# Mazebot.net
KiCad netlist of a schematic drawn in Altium Designer
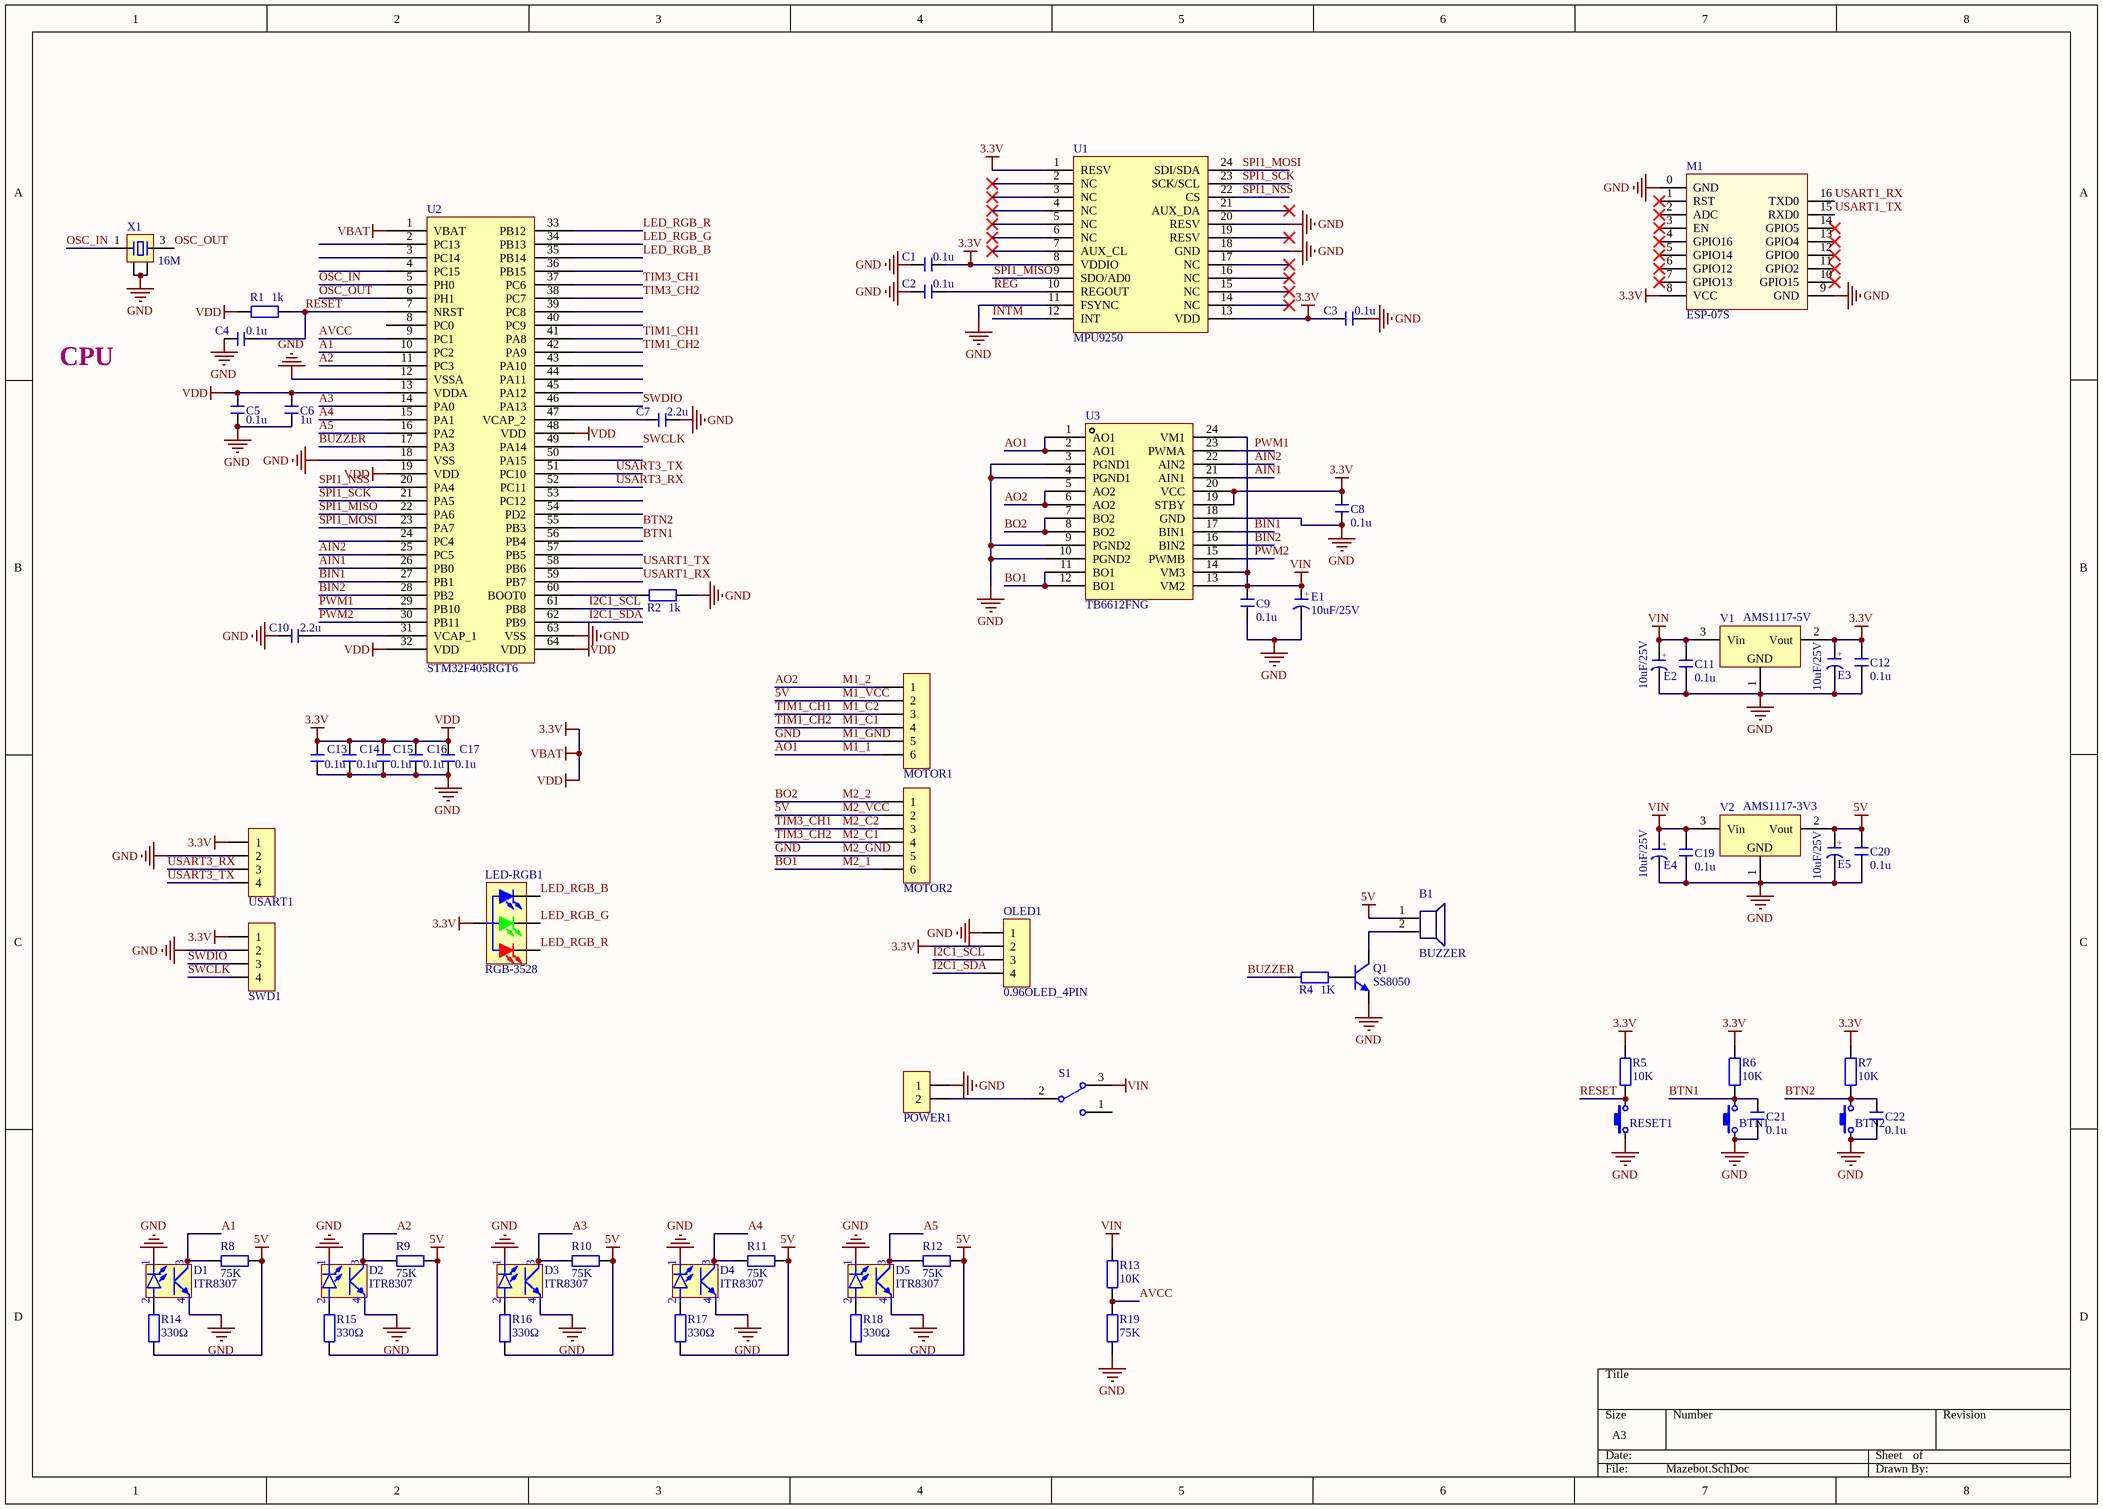
[diagram p0: Mazebot.SchDoc]

(export (version "E")
  (design (tool "Eeschema 10.0.6"))
  (components
    (comp (ref "B1")
      (value "BUZZER")
      (footprint "BUZ-TH_BD9.0-P4.00-D1.0-FD")
      (description "小蜂鸣器 脚距4mm")
      (libsource (lib "0.0 - YltsSchlib") (part "BUZZER"))
    )
    (comp (ref "BTN1")
      (value "ButtonTACT_3x4x2_180")
      (footprint "ButtonTACT_3x4x2_180H")
      (description "Button")
      (libsource (lib "0.0 - YltsSchlib") (part "ButtonTACT_3x4x2_180"))
    )
    (comp (ref "BTN2")
      (value "ButtonTACT_3x4x2_180")
      (footprint "ButtonTACT_3x4x2_180H")
      (description "Button")
      (libsource (lib "0.0 - YltsSchlib") (part "ButtonTACT_3x4x2_180"))
    )
    (comp (ref "C1")
      (value "0.1u")
      (footprint "0603-CAP")
      (description "贴片电容")
      (libsource (lib "0.1 - 电阻-电容-电感") (part "C"))
    )
    (comp (ref "C2")
      (value "0.1u")
      (footprint "0603-CAP")
      (description "贴片电容")
      (libsource (lib "0.1 - 电阻-电容-电感") (part "C"))
    )
    (comp (ref "C3")
      (value "0.1u")
      (footprint "0603-CAP")
      (description "贴片电容")
      (libsource (lib "0.1 - 电阻-电容-电感") (part "C"))
    )
    (comp (ref "C4")
      (value "0.1u")
      (footprint "0603-CAP")
      (description "贴片电容")
      (libsource (lib "0.1 - 电阻-电容-电感") (part "C"))
    )
    (comp (ref "C5")
      (value "0.1u")
      (footprint "0603-CAP")
      (description "贴片电容")
      (libsource (lib "0.1 - 电阻-电容-电感") (part "C"))
    )
    (comp (ref "C6")
      (value "1u")
      (footprint "0603-CAP")
      (description "贴片电容")
      (libsource (lib "0.1 - 电阻-电容-电感") (part "C"))
    )
    (comp (ref "C7")
      (value "2.2u")
      (footprint "0603-CAP")
      (description "贴片电容")
      (libsource (lib "0.1 - 电阻-电容-电感") (part "C"))
    )
    (comp (ref "C8")
      (value "0.1u")
      (footprint "0603-CAP")
      (description "贴片电容")
      (libsource (lib "0.1 - 电阻-电容-电感") (part "C"))
    )
    (comp (ref "C9")
      (value "0.1u")
      (footprint "0603-CAP")
      (description "贴片电容")
      (libsource (lib "0.1 - 电阻-电容-电感") (part "C"))
    )
    (comp (ref "C10")
      (value "2.2u")
      (footprint "0603-CAP")
      (description "贴片电容")
      (libsource (lib "0.1 - 电阻-电容-电感") (part "C"))
    )
    (comp (ref "C11")
      (value "0.1u")
      (footprint "0603-CAP")
      (description "贴片电容")
      (libsource (lib "0.1 - 电阻-电容-电感") (part "C"))
    )
    (comp (ref "C12")
      (value "0.1u")
      (footprint "0603-CAP")
      (description "贴片电容")
      (libsource (lib "0.1 - 电阻-电容-电感") (part "C"))
    )
    (comp (ref "C13")
      (value "0.1u")
      (footprint "0603-CAP")
      (description "贴片电容")
      (libsource (lib "0.1 - 电阻-电容-电感") (part "C"))
    )
    (comp (ref "C14")
      (value "0.1u")
      (footprint "0603-CAP")
      (description "贴片电容")
      (libsource (lib "0.1 - 电阻-电容-电感") (part "C"))
    )
    (comp (ref "C15")
      (value "0.1u")
      (footprint "0603-CAP")
      (description "贴片电容")
      (libsource (lib "0.1 - 电阻-电容-电感") (part "C"))
    )
    (comp (ref "C16")
      (value "0.1u")
      (footprint "0603-CAP")
      (description "贴片电容")
      (libsource (lib "0.1 - 电阻-电容-电感") (part "C"))
    )
    (comp (ref "C17")
      (value "0.1u")
      (footprint "0603-CAP")
      (description "贴片电容")
      (libsource (lib "0.1 - 电阻-电容-电感") (part "C"))
    )
    (comp (ref "C19")
      (value "0.1u")
      (footprint "0603-CAP")
      (description "贴片电容")
      (libsource (lib "0.1 - 电阻-电容-电感") (part "C"))
    )
    (comp (ref "C20")
      (value "0.1u")
      (footprint "0603-CAP")
      (description "贴片电容")
      (libsource (lib "0.1 - 电阻-电容-电感") (part "C"))
    )
    (comp (ref "C21")
      (value "0.1u")
      (footprint "0603-CAP")
      (description "贴片电容")
      (libsource (lib "0.1 - 电阻-电容-电感") (part "C"))
    )
    (comp (ref "C22")
      (value "0.1u")
      (footprint "0603-CAP")
      (description "贴片电容")
      (libsource (lib "0.1 - 电阻-电容-电感") (part "C"))
    )
    (comp (ref "D1")
      (value "ITR8307")
      (footprint "OPTO-SMD_ITR8307")
      (description "反射式光电开关 收发一体")
      (libsource (lib "0.0 - YltsSchlib") (part "ITR8307"))
    )
    (comp (ref "D2")
      (value "ITR8307")
      (footprint "OPTO-SMD_ITR8307")
      (description "反射式光电开关 收发一体")
      (libsource (lib "0.0 - YltsSchlib") (part "ITR8307"))
    )
    (comp (ref "D3")
      (value "ITR8307")
      (footprint "OPTO-SMD_ITR8307")
      (description "反射式光电开关 收发一体")
      (libsource (lib "0.0 - YltsSchlib") (part "ITR8307"))
    )
    (comp (ref "D4")
      (value "ITR8307")
      (footprint "OPTO-SMD_ITR8307")
      (description "反射式光电开关 收发一体")
      (libsource (lib "0.0 - YltsSchlib") (part "ITR8307"))
    )
    (comp (ref "D5")
      (value "ITR8307")
      (footprint "OPTO-SMD_ITR8307")
      (description "反射式光电开关 收发一体")
      (libsource (lib "0.0 - YltsSchlib") (part "ITR8307"))
    )
    (comp (ref "E1")
      (value "10uF/25V")
      (footprint "3528-CAP")
      (description "贴片钽电容")
      (libsource (lib "0.1 - 电阻-电容-电感") (part "CT"))
    )
    (comp (ref "E2")
      (value "10uF/25V")
      (footprint "3528-CAP")
      (description "贴片钽电容")
      (libsource (lib "0.1 - 电阻-电容-电感") (part "CT"))
    )
    (comp (ref "E3")
      (value "10uF/25V")
      (footprint "3528-CAP")
      (description "贴片钽电容")
      (libsource (lib "0.1 - 电阻-电容-电感") (part "CT"))
    )
    (comp (ref "E4")
      (value "10uF/25V")
      (footprint "3528-CAP")
      (description "贴片钽电容")
      (libsource (lib "0.1 - 电阻-电容-电感") (part "CT"))
    )
    (comp (ref "E5")
      (value "10uF/25V")
      (footprint "3528-CAP")
      (description "贴片钽电容")
      (libsource (lib "0.1 - 电阻-电容-电感") (part "CT"))
    )
    (comp (ref "LED-RGB1")
      (value "RGB-3528")
      (footprint "LED 3528-4Pin")
      (description "3528三基色LED")
      (fields (field (name "版权归属") "封装库来自淘宝 ID：黄晶宝石"))
      (libsource (lib "0.3 - LED发光二极管") (part "LED-RGB 3528"))
    )
    (comp (ref "M1")
      (value "ESP-07S")
      (footprint "ESP-07S")
      (libsource (lib "0.0 - YltsSchlib") (part "ESP-07S"))
    )
    (comp (ref "MOTOR1")
      (value "HDR-1X6")
      (footprint "HDR2.54-M-LI-6P")
      (description "6P接插件")
      (fields (field (name "版权归属") "封装库来自淘宝 ID：黄晶宝石"))
      (libsource (lib "5.3 - 接插件-脚距2.54 (100mil) ") (part "Header 6"))
    )
    (comp (ref "MOTOR2")
      (value "HDR-1X6")
      (footprint "HDR2.54-M-LI-6P")
      (description "6P接插件")
      (fields (field (name "版权归属") "封装库来自淘宝 ID：黄晶宝石"))
      (libsource (lib "5.3 - 接插件-脚距2.54 (100mil) ") (part "Header 6"))
    )
    (comp (ref "OLED1")
      (value "0.96OLED_4PIN")
      (footprint "0.96OLED_4PIN")
      (libsource (lib "0.0 - YltsSchlib") (part "0.96OLED_4PIN"))
    )
    (comp (ref "POWER1")
      (value "HDR-1X2")
      (footprint "XH2.54-LI-2P")
      (description "2P接插件")
      (fields (field (name "版权归属") "封装库来自淘宝 ID：黄晶宝石"))
      (libsource (lib "5.3 - 接插件-脚距2.54 (100mil) ") (part "Header 2"))
    )
    (comp (ref "Q1")
      (value "SS8050")
      (footprint "SOT23-3N")
      (description "高频放大-NPN型")
      (fields (field (name "版权归属") "封装库来自淘宝 ID：黄晶宝石"))
      (libsource (lib "0.4 - 三极管") (part "8050-SMD"))
    )
    (comp (ref "R1")
      (value "1k")
      (footprint "0603-RES")
      (description "贴片电阻")
      (fields (field (name "版权归属") "来自淘宝 ID：黄晶宝石"))
      (libsource (lib "0.1 - 电阻-电容-电感") (part "R"))
    )
    (comp (ref "R2")
      (value "1k")
      (footprint "0603-RES")
      (description "贴片电阻")
      (fields (field (name "版权归属") "来自淘宝 ID：黄晶宝石"))
      (libsource (lib "0.1 - 电阻-电容-电感") (part "R"))
    )
    (comp (ref "R4")
      (value "1K")
      (footprint "0603-RES")
      (description "贴片电阻")
      (fields (field (name "版权归属") "来自淘宝 ID：黄晶宝石"))
      (libsource (lib "0.1 - 电阻-电容-电感") (part "R"))
    )
    (comp (ref "R5")
      (value "10K")
      (footprint "0603-RES")
      (description "贴片电阻")
      (fields (field (name "版权归属") "来自淘宝 ID：黄晶宝石"))
      (libsource (lib "0.1 - 电阻-电容-电感") (part "R"))
    )
    (comp (ref "R6")
      (value "10K")
      (footprint "0603-RES")
      (description "贴片电阻")
      (fields (field (name "版权归属") "来自淘宝 ID：黄晶宝石"))
      (libsource (lib "0.1 - 电阻-电容-电感") (part "R"))
    )
    (comp (ref "R7")
      (value "10K")
      (footprint "0603-RES")
      (description "贴片电阻")
      (fields (field (name "版权归属") "来自淘宝 ID：黄晶宝石"))
      (libsource (lib "0.1 - 电阻-电容-电感") (part "R"))
    )
    (comp (ref "R8")
      (value "75K")
      (footprint "0603-RES")
      (description "贴片电阻")
      (fields (field (name "版权归属") "来自淘宝 ID：黄晶宝石"))
      (libsource (lib "0.1 - 电阻-电容-电感") (part "R"))
    )
    (comp (ref "R9")
      (value "75K")
      (footprint "0603-RES")
      (description "贴片电阻")
      (fields (field (name "版权归属") "来自淘宝 ID：黄晶宝石"))
      (libsource (lib "0.1 - 电阻-电容-电感") (part "R"))
    )
    (comp (ref "R10")
      (value "75K")
      (footprint "0603-RES")
      (description "贴片电阻")
      (fields (field (name "版权归属") "来自淘宝 ID：黄晶宝石"))
      (libsource (lib "0.1 - 电阻-电容-电感") (part "R"))
    )
    (comp (ref "R11")
      (value "75K")
      (footprint "0603-RES")
      (description "贴片电阻")
      (fields (field (name "版权归属") "来自淘宝 ID：黄晶宝石"))
      (libsource (lib "0.1 - 电阻-电容-电感") (part "R"))
    )
    (comp (ref "R12")
      (value "75K")
      (footprint "0603-RES")
      (description "贴片电阻")
      (fields (field (name "版权归属") "来自淘宝 ID：黄晶宝石"))
      (libsource (lib "0.1 - 电阻-电容-电感") (part "R"))
    )
    (comp (ref "R13")
      (value "10K")
      (footprint "0603-RES")
      (description "贴片电阻")
      (fields (field (name "版权归属") "来自淘宝 ID：黄晶宝石"))
      (libsource (lib "0.1 - 电阻-电容-电感") (part "R"))
    )
    (comp (ref "R14")
      (value "330Ω")
      (footprint "0603-RES")
      (description "贴片电阻")
      (fields (field (name "版权归属") "来自淘宝 ID：黄晶宝石"))
      (libsource (lib "0.1 - 电阻-电容-电感") (part "R"))
    )
    (comp (ref "R15")
      (value "330Ω")
      (footprint "0603-RES")
      (description "贴片电阻")
      (fields (field (name "版权归属") "来自淘宝 ID：黄晶宝石"))
      (libsource (lib "0.1 - 电阻-电容-电感") (part "R"))
    )
    (comp (ref "R16")
      (value "330Ω")
      (footprint "0603-RES")
      (description "贴片电阻")
      (fields (field (name "版权归属") "来自淘宝 ID：黄晶宝石"))
      (libsource (lib "0.1 - 电阻-电容-电感") (part "R"))
    )
    (comp (ref "R17")
      (value "330Ω")
      (footprint "0603-RES")
      (description "贴片电阻")
      (fields (field (name "版权归属") "来自淘宝 ID：黄晶宝石"))
      (libsource (lib "0.1 - 电阻-电容-电感") (part "R"))
    )
    (comp (ref "R18")
      (value "330Ω")
      (footprint "0603-RES")
      (description "贴片电阻")
      (fields (field (name "版权归属") "来自淘宝 ID：黄晶宝石"))
      (libsource (lib "0.1 - 电阻-电容-电感") (part "R"))
    )
    (comp (ref "R19")
      (value "75K")
      (footprint "0603-RES")
      (description "贴片电阻")
      (fields (field (name "版权归属") "来自淘宝 ID：黄晶宝石"))
      (libsource (lib "0.1 - 电阻-电容-电感") (part "R"))
    )
    (comp (ref "RESET1")
      (value "ButtonTACT_3x4x2_180")
      (footprint "ButtonTACT_3x4x2_180H")
      (description "Button")
      (libsource (lib "0.0 - YltsSchlib") (part "ButtonTACT_3x4x2_180"))
    )
    (comp (ref "S1")
      (value "SwitchSPDT_4.3x8.6_D90")
      (footprint "SwitchSPDT_4.3X8.6_D90")
      (description "Switch")
      (libsource (lib "0.0 - YltsSchlib") (part "SwitchSPDT_4.3x8.6_D90"))
    )
    (comp (ref "SWD1")
      (value "HDR-1X4")
      (footprint "HDR2.54-LI-4P")
      (description "4P接插件")
      (fields (field (name "版权归属") "封装库来自淘宝 ID：黄晶宝石"))
      (libsource (lib "5.3 - 接插件-脚距2.54 (100mil) ") (part "Header 4"))
    )
    (comp (ref "U1")
      (value "MPU9250")
      (footprint "QFN_P0.4_24")
      (description "9轴姿态传感器")
      (libsource (lib "0.0 - YltsSchlib") (part "MPU925x"))
    )
    (comp (ref "U2")
      (value "STM32F405RGT6")
      (footprint "LQFP-64")
      (libsource (lib "陀螺仪 元件") (part "STM32F405RGT7"))
    )
    (comp (ref "U3")
      (value "TB6612FNG")
      (footprint "SSOP24_N")
      (description "双直流电机驱动器")
      (libsource (lib "0.0 - YltsSchlib") (part "TB6612FNG"))
    )
    (comp (ref "USART1")
      (value "HDR-1X4")
      (footprint "HDR2.54-LI-4P")
      (description "4P接插件")
      (fields (field (name "版权归属") "封装库来自淘宝 ID：黄晶宝石"))
      (libsource (lib "5.3 - 接插件-脚距2.54 (100mil) ") (part "Header 4"))
    )
    (comp (ref "V1")
      (value "AMS1117-5V")
      (footprint "SOT223_L")
      (description "三端稳压芯片")
      (libsource (lib "1.1 - 电源类芯片") (part "AMS1117"))
    )
    (comp (ref "V2")
      (value "AMS1117-3V3")
      (footprint "SOT223_L")
      (description "三端稳压芯片")
      (libsource (lib "1.1 - 电源类芯片") (part "AMS1117"))
    )
    (comp (ref "X1")
      (value "16M")
      (footprint "OSC 3225-4P")
      (description "4脚无源晶振")
      (fields (field (name "版权归属") "封装库来自淘宝卖家 ID：黄晶宝石"))
      (libsource (lib "2.0 - 保险丝-晶振-光耦") (part "XTAL-4P"))
    )
  )
  (nets
    (net (code "1") (name "/A1") (class "Default")
      (node (ref "D1") (pin "3") (pinfunction "K_3") (pintype "passive"))
      (node (ref "R8") (pin "2") (pinfunction "2_2") (pintype "passive"))
      (node (ref "U2") (pin "10") (pinfunction "PC2_10") (pintype "passive"))
    )
    (net (code "2") (name "/A2") (class "Default")
      (node (ref "D2") (pin "3") (pinfunction "K_3") (pintype "passive"))
      (node (ref "R9") (pin "2") (pinfunction "2_2") (pintype "passive"))
      (node (ref "U2") (pin "11") (pinfunction "PC3_11") (pintype "passive"))
    )
    (net (code "3") (name "/A3") (class "Default")
      (node (ref "D3") (pin "3") (pinfunction "K_3") (pintype "passive"))
      (node (ref "R10") (pin "2") (pinfunction "2_2") (pintype "passive"))
      (node (ref "U2") (pin "14") (pinfunction "PA0_14") (pintype "passive"))
    )
    (net (code "4") (name "/A4") (class "Default")
      (node (ref "D4") (pin "3") (pinfunction "K_3") (pintype "passive"))
      (node (ref "R11") (pin "2") (pinfunction "2_2") (pintype "passive"))
      (node (ref "U2") (pin "15") (pinfunction "PA1_15") (pintype "passive"))
    )
    (net (code "5") (name "/A5") (class "Default")
      (node (ref "D5") (pin "3") (pinfunction "K_3") (pintype "passive"))
      (node (ref "R12") (pin "2") (pinfunction "2_2") (pintype "passive"))
      (node (ref "U2") (pin "16") (pinfunction "PA2_16") (pintype "passive"))
    )
    (net (code "6") (name "/AIN1") (class "Default")
      (node (ref "U2") (pin "26") (pinfunction "PB0_26") (pintype "passive"))
      (node (ref "U3") (pin "21") (pinfunction "AIN1_21") (pintype "passive"))
    )
    (net (code "7") (name "/AIN2") (class "Default")
      (node (ref "U2") (pin "25") (pinfunction "PC5_25") (pintype "passive"))
      (node (ref "U3") (pin "22") (pinfunction "AIN2_22") (pintype "passive"))
    )
    (net (code "8") (name "/AO1") (class "Default")
      (node (ref "MOTOR1") (pin "6") (pinfunction "6_6") (pintype "passive"))
      (node (ref "U3") (pin "1") (pinfunction "AO1_1") (pintype "passive"))
      (node (ref "U3") (pin "2") (pinfunction "AO1_2") (pintype "passive"))
    )
    (net (code "9") (name "/AO2") (class "Default")
      (node (ref "MOTOR1") (pin "1") (pinfunction "1_1") (pintype "passive"))
      (node (ref "U3") (pin "5") (pinfunction "AO2_5") (pintype "passive"))
      (node (ref "U3") (pin "6") (pinfunction "AO2_6") (pintype "passive"))
    )
    (net (code "10") (name "/AVCC") (class "Default")
      (node (ref "R13") (pin "2") (pinfunction "2_2") (pintype "passive"))
      (node (ref "R19") (pin "1") (pinfunction "1_1") (pintype "passive"))
      (node (ref "U2") (pin "9") (pinfunction "PC1_9") (pintype "passive"))
    )
    (net (code "11") (name "/BIN1") (class "Default")
      (node (ref "U2") (pin "27") (pinfunction "PB1_27") (pintype "passive"))
      (node (ref "U3") (pin "17") (pinfunction "BIN1_17") (pintype "passive"))
    )
    (net (code "12") (name "/BIN2") (class "Default")
      (node (ref "U2") (pin "28") (pinfunction "PB2_28") (pintype "passive"))
      (node (ref "U3") (pin "16") (pinfunction "BIN2_16") (pintype "passive"))
    )
    (net (code "13") (name "/BO1") (class "Default")
      (node (ref "MOTOR2") (pin "6") (pinfunction "6_6") (pintype "passive"))
      (node (ref "U3") (pin "11") (pinfunction "BO1_11") (pintype "passive"))
      (node (ref "U3") (pin "12") (pinfunction "BO1_12") (pintype "passive"))
    )
    (net (code "14") (name "/BO2") (class "Default")
      (node (ref "MOTOR2") (pin "1") (pinfunction "1_1") (pintype "passive"))
      (node (ref "U3") (pin "7") (pinfunction "BO2_7") (pintype "passive"))
      (node (ref "U3") (pin "8") (pinfunction "BO2_8") (pintype "passive"))
    )
    (net (code "15") (name "/BTN1") (class "Default")
      (node (ref "BTN1") (pin "2") (pinfunction "2_2") (pintype "passive"))
      (node (ref "C21") (pin "2") (pinfunction "2_2") (pintype "passive"))
      (node (ref "R6") (pin "2") (pinfunction "2_2") (pintype "passive"))
      (node (ref "U2") (pin "56") (pinfunction "PB4_56") (pintype "passive"))
    )
    (net (code "16") (name "/BTN2") (class "Default")
      (node (ref "BTN2") (pin "2") (pinfunction "2_2") (pintype "passive"))
      (node (ref "C22") (pin "2") (pinfunction "2_2") (pintype "passive"))
      (node (ref "R7") (pin "2") (pinfunction "2_2") (pintype "passive"))
      (node (ref "U2") (pin "55") (pinfunction "PB3_55") (pintype "passive"))
    )
    (net (code "17") (name "/BUZZER") (class "Default")
      (node (ref "R4") (pin "2") (pinfunction "2_2") (pintype "passive"))
      (node (ref "U2") (pin "17") (pinfunction "PA3_17") (pintype "passive"))
    )
    (net (code "18") (name "/I2C1_SCL") (class "Default")
      (node (ref "OLED1") (pin "3") (pinfunction "3_3") (pintype "passive"))
      (node (ref "U2") (pin "61") (pinfunction "PB8_61") (pintype "passive"))
    )
    (net (code "19") (name "/I2C1_SDA") (class "Default")
      (node (ref "OLED1") (pin "4") (pinfunction "4_4") (pintype "passive"))
      (node (ref "U2") (pin "62") (pinfunction "PB9_62") (pintype "passive"))
    )
    (net (code "20") (name "/INTM") (class "Default")
      (node (ref "U1") (pin "12") (pinfunction "INT_12") (pintype "passive"))
    )
    (net (code "21") (name "/LED_RGB_B") (class "Default")
      (node (ref "LED-RGB1") (pin "3") (pinfunction "BULE_K_3") (pintype "passive"))
      (node (ref "U2") (pin "35") (pinfunction "PB14_35") (pintype "passive"))
    )
    (net (code "22") (name "/LED_RGB_G") (class "Default")
      (node (ref "LED-RGB1") (pin "2") (pinfunction "GREEN_K_2") (pintype "passive"))
      (node (ref "U2") (pin "34") (pinfunction "PB13_34") (pintype "passive"))
    )
    (net (code "23") (name "/LED_RGB_R") (class "Default")
      (node (ref "LED-RGB1") (pin "1") (pinfunction "RED_K_1") (pintype "passive"))
      (node (ref "U2") (pin "33") (pinfunction "PB12_33") (pintype "passive"))
    )
    (net (code "24") (name "/M1_C1") (class "Default")
      (node (ref "MOTOR1") (pin "4") (pinfunction "4_4") (pintype "passive"))
      (node (ref "U2") (pin "42") (pinfunction "PA9_42") (pintype "passive"))
    )
    (net (code "25") (name "/M1_C2") (class "Default")
      (node (ref "MOTOR1") (pin "3") (pinfunction "3_3") (pintype "passive"))
      (node (ref "U2") (pin "41") (pinfunction "PA8_41") (pintype "passive"))
    )
    (net (code "26") (name "/M2_C1") (class "Default")
      (node (ref "MOTOR2") (pin "4") (pinfunction "4_4") (pintype "passive"))
      (node (ref "U2") (pin "38") (pinfunction "PC7_38") (pintype "passive"))
    )
    (net (code "27") (name "/M2_C2") (class "Default")
      (node (ref "MOTOR2") (pin "3") (pinfunction "3_3") (pintype "passive"))
      (node (ref "U2") (pin "37") (pinfunction "PC6_37") (pintype "passive"))
    )
    (net (code "28") (name "/OSC_IN") (class "Default")
      (node (ref "U2") (pin "5") (pinfunction "PH0_5") (pintype "passive"))
      (node (ref "X1") (pin "1") (pinfunction "1_1") (pintype "passive"))
    )
    (net (code "29") (name "/OSC_OUT") (class "Default")
      (node (ref "U2") (pin "6") (pinfunction "PH1_6") (pintype "passive"))
      (node (ref "X1") (pin "3") (pinfunction "3_3") (pintype "passive"))
    )
    (net (code "30") (name "/PWM1") (class "Default")
      (node (ref "U2") (pin "29") (pinfunction "PB10_29") (pintype "passive"))
      (node (ref "U3") (pin "23") (pinfunction "PWMA_23") (pintype "passive"))
    )
    (net (code "31") (name "/PWM2") (class "Default")
      (node (ref "U2") (pin "30") (pinfunction "PB11_30") (pintype "passive"))
      (node (ref "U3") (pin "15") (pinfunction "PWMB_15") (pintype "passive"))
    )
    (net (code "32") (name "/REG") (class "Default")
      (node (ref "C2") (pin "1") (pinfunction "1_1") (pintype "passive"))
      (node (ref "U1") (pin "10") (pinfunction "REGOUT_10") (pintype "passive"))
    )
    (net (code "33") (name "/RESET") (class "Default")
      (node (ref "C4") (pin "1") (pinfunction "1_1") (pintype "passive"))
      (node (ref "R1") (pin "1") (pinfunction "1_1") (pintype "passive"))
      (node (ref "R5") (pin "2") (pinfunction "2_2") (pintype "passive"))
      (node (ref "RESET1") (pin "2") (pinfunction "2_2") (pintype "passive"))
      (node (ref "U2") (pin "7") (pinfunction "NRST_7") (pintype "passive"))
    )
    (net (code "34") (name "/SPI1_MISO") (class "Default")
      (node (ref "U1") (pin "9") (pinfunction "SDO/AD0_9") (pintype "passive"))
      (node (ref "U2") (pin "22") (pinfunction "PA6_22") (pintype "passive"))
    )
    (net (code "35") (name "/SPI1_MOSI") (class "Default")
      (node (ref "U1") (pin "24") (pinfunction "SDI/SDA_24") (pintype "passive"))
      (node (ref "U2") (pin "23") (pinfunction "PA7_23") (pintype "passive"))
    )
    (net (code "36") (name "/SPI1_NSS") (class "Default")
      (node (ref "U1") (pin "22") (pinfunction "CS_22") (pintype "passive"))
      (node (ref "U2") (pin "20") (pinfunction "PA4_20") (pintype "passive"))
    )
    (net (code "37") (name "/SPI1_SCK") (class "Default")
      (node (ref "U1") (pin "23") (pinfunction "SCK/SCL_23") (pintype "passive"))
      (node (ref "U2") (pin "21") (pinfunction "PA5_21") (pintype "passive"))
    )
    (net (code "38") (name "/SWCLK") (class "Default")
      (node (ref "SWD1") (pin "4") (pinfunction "4_4") (pintype "passive"))
      (node (ref "U2") (pin "49") (pinfunction "PA14_49") (pintype "passive"))
    )
    (net (code "39") (name "/SWDIO") (class "Default")
      (node (ref "SWD1") (pin "3") (pinfunction "3_3") (pintype "passive"))
      (node (ref "U2") (pin "46") (pinfunction "PA13_46") (pintype "passive"))
    )
    (net (code "40") (name "/USART1_RX") (class "Default")
      (node (ref "M1") (pin "16") (pinfunction "TXD0_16") (pintype "passive"))
      (node (ref "U2") (pin "59") (pinfunction "PB7_59") (pintype "passive"))
    )
    (net (code "41") (name "/USART1_TX") (class "Default")
      (node (ref "M1") (pin "15") (pinfunction "RXD0_15") (pintype "passive"))
      (node (ref "U2") (pin "58") (pinfunction "PB6_58") (pintype "passive"))
    )
    (net (code "42") (name "/USART3_RX") (class "Default")
      (node (ref "U2") (pin "52") (pinfunction "PC11_52") (pintype "passive"))
      (node (ref "USART1") (pin "3") (pinfunction "3_3") (pintype "passive"))
    )
    (net (code "43") (name "/USART3_TX") (class "Default")
      (node (ref "U2") (pin "51") (pinfunction "PC10_51") (pintype "passive"))
      (node (ref "USART1") (pin "4") (pinfunction "4_4") (pintype "passive"))
    )
    (net (code "44") (name "3.3V") (class "Default")
      (node (ref "C1") (pin "1") (pinfunction "1_1") (pintype "passive"))
      (node (ref "C12") (pin "2") (pinfunction "2_2") (pintype "passive"))
      (node (ref "C13") (pin "1") (pinfunction "1_1") (pintype "passive"))
      (node (ref "C14") (pin "1") (pinfunction "1_1") (pintype "passive"))
      (node (ref "C15") (pin "1") (pinfunction "1_1") (pintype "passive"))
      (node (ref "C16") (pin "1") (pinfunction "1_1") (pintype "passive"))
      (node (ref "C17") (pin "1") (pinfunction "1_1") (pintype "passive"))
      (node (ref "C3") (pin "2") (pinfunction "2_2") (pintype "passive"))
      (node (ref "C5") (pin "1") (pinfunction "1_1") (pintype "passive"))
      (node (ref "C6") (pin "1") (pinfunction "1_1") (pintype "passive"))
      (node (ref "C8") (pin "2") (pinfunction "2_2") (pintype "passive"))
      (node (ref "E3") (pin "1") (pinfunction "A_1") (pintype "passive"))
      (node (ref "LED-RGB1") (pin "4") (pinfunction "A_4") (pintype "passive"))
      (node (ref "M1") (pin "8") (pinfunction "VCC_8") (pintype "passive"))
      (node (ref "OLED1") (pin "2") (pinfunction "2_2") (pintype "passive"))
      (node (ref "R1") (pin "2") (pinfunction "2_2") (pintype "passive"))
      (node (ref "R5") (pin "1") (pinfunction "1_1") (pintype "passive"))
      (node (ref "R6") (pin "1") (pinfunction "1_1") (pintype "passive"))
      (node (ref "R7") (pin "1") (pinfunction "1_1") (pintype "passive"))
      (node (ref "SWD1") (pin "1") (pinfunction "1_1") (pintype "passive"))
      (node (ref "U1") (pin "1") (pinfunction "RESV_1") (pintype "passive"))
      (node (ref "U1") (pin "13") (pinfunction "VDD_13") (pintype "passive"))
      (node (ref "U1") (pin "8") (pinfunction "VDDIO_8") (pintype "passive"))
      (node (ref "U2") (pin "1") (pinfunction "VBAT_1") (pintype "passive"))
      (node (ref "U2") (pin "13") (pinfunction "VDDA_13") (pintype "passive"))
      (node (ref "U2") (pin "19") (pinfunction "VDD_19") (pintype "passive"))
      (node (ref "U2") (pin "32") (pinfunction "VDD_32") (pintype "passive"))
      (node (ref "U2") (pin "48") (pinfunction "VDD_48") (pintype "passive"))
      (node (ref "U2") (pin "64") (pinfunction "VDD_64") (pintype "passive"))
      (node (ref "U3") (pin "19") (pinfunction "STBY_19") (pintype "passive"))
      (node (ref "U3") (pin "20") (pinfunction "VCC_20") (pintype "passive"))
      (node (ref "USART1") (pin "1") (pinfunction "1_1") (pintype "passive"))
      (node (ref "V1") (pin "2") (pinfunction "Vout_2") (pintype "passive"))
    )
    (net (code "45") (name "5V") (class "Default")
      (node (ref "B1") (pin "1") (pinfunction "VCC_1") (pintype "passive"))
      (node (ref "C20") (pin "2") (pinfunction "2_2") (pintype "passive"))
      (node (ref "E5") (pin "1") (pinfunction "A_1") (pintype "passive"))
      (node (ref "MOTOR1") (pin "2") (pinfunction "2_2") (pintype "passive"))
      (node (ref "MOTOR2") (pin "2") (pinfunction "2_2") (pintype "passive"))
      (node (ref "R10") (pin "1") (pinfunction "1_1") (pintype "passive"))
      (node (ref "R11") (pin "1") (pinfunction "1_1") (pintype "passive"))
      (node (ref "R12") (pin "1") (pinfunction "1_1") (pintype "passive"))
      (node (ref "R14") (pin "1") (pinfunction "1_1") (pintype "passive"))
      (node (ref "R15") (pin "1") (pinfunction "1_1") (pintype "passive"))
      (node (ref "R16") (pin "1") (pinfunction "1_1") (pintype "passive"))
      (node (ref "R17") (pin "1") (pinfunction "1_1") (pintype "passive"))
      (node (ref "R18") (pin "1") (pinfunction "1_1") (pintype "passive"))
      (node (ref "R8") (pin "1") (pinfunction "1_1") (pintype "passive"))
      (node (ref "R9") (pin "1") (pinfunction "1_1") (pintype "passive"))
      (node (ref "V2") (pin "2") (pinfunction "Vout_2") (pintype "passive"))
    )
    (net (code "46") (name "GND") (class "Default")
      (node (ref "BTN1") (pin "1") (pinfunction "1_1") (pintype "passive"))
      (node (ref "BTN2") (pin "1") (pinfunction "1_1") (pintype "passive"))
      (node (ref "C1") (pin "2") (pinfunction "2_2") (pintype "passive"))
      (node (ref "C10") (pin "2") (pinfunction "2_2") (pintype "passive"))
      (node (ref "C11") (pin "1") (pinfunction "1_1") (pintype "passive"))
      (node (ref "C12") (pin "1") (pinfunction "1_1") (pintype "passive"))
      (node (ref "C13") (pin "2") (pinfunction "2_2") (pintype "passive"))
      (node (ref "C14") (pin "2") (pinfunction "2_2") (pintype "passive"))
      (node (ref "C15") (pin "2") (pinfunction "2_2") (pintype "passive"))
      (node (ref "C16") (pin "2") (pinfunction "2_2") (pintype "passive"))
      (node (ref "C17") (pin "2") (pinfunction "2_2") (pintype "passive"))
      (node (ref "C19") (pin "1") (pinfunction "1_1") (pintype "passive"))
      (node (ref "C2") (pin "2") (pinfunction "2_2") (pintype "passive"))
      (node (ref "C20") (pin "1") (pinfunction "1_1") (pintype "passive"))
      (node (ref "C21") (pin "1") (pinfunction "1_1") (pintype "passive"))
      (node (ref "C22") (pin "1") (pinfunction "1_1") (pintype "passive"))
      (node (ref "C3") (pin "1") (pinfunction "1_1") (pintype "passive"))
      (node (ref "C4") (pin "2") (pinfunction "2_2") (pintype "passive"))
      (node (ref "C5") (pin "2") (pinfunction "2_2") (pintype "passive"))
      (node (ref "C6") (pin "2") (pinfunction "2_2") (pintype "passive"))
      (node (ref "C7") (pin "1") (pinfunction "1_1") (pintype "passive"))
      (node (ref "C8") (pin "1") (pinfunction "1_1") (pintype "passive"))
      (node (ref "C9") (pin "1") (pinfunction "1_1") (pintype "passive"))
      (node (ref "D1") (pin "1") (pinfunction "K_1") (pintype "passive"))
      (node (ref "D1") (pin "4") (pinfunction "K_4") (pintype "passive"))
      (node (ref "D2") (pin "1") (pinfunction "K_1") (pintype "passive"))
      (node (ref "D2") (pin "4") (pinfunction "K_4") (pintype "passive"))
      (node (ref "D3") (pin "1") (pinfunction "K_1") (pintype "passive"))
      (node (ref "D3") (pin "4") (pinfunction "K_4") (pintype "passive"))
      (node (ref "D4") (pin "1") (pinfunction "K_1") (pintype "passive"))
      (node (ref "D4") (pin "4") (pinfunction "K_4") (pintype "passive"))
      (node (ref "D5") (pin "1") (pinfunction "K_1") (pintype "passive"))
      (node (ref "D5") (pin "4") (pinfunction "K_4") (pintype "passive"))
      (node (ref "E1") (pin "2") (pinfunction "K_2") (pintype "passive"))
      (node (ref "E2") (pin "2") (pinfunction "K_2") (pintype "passive"))
      (node (ref "E3") (pin "2") (pinfunction "K_2") (pintype "passive"))
      (node (ref "E4") (pin "2") (pinfunction "K_2") (pintype "passive"))
      (node (ref "E5") (pin "2") (pinfunction "K_2") (pintype "passive"))
      (node (ref "M1") (pin "0") (pinfunction "GND_0") (pintype "passive"))
      (node (ref "M1") (pin "9") (pinfunction "GND_9") (pintype "passive"))
      (node (ref "MOTOR1") (pin "5") (pinfunction "5_5") (pintype "passive"))
      (node (ref "MOTOR2") (pin "5") (pinfunction "5_5") (pintype "passive"))
      (node (ref "OLED1") (pin "1") (pinfunction "1_1") (pintype "passive"))
      (node (ref "POWER1") (pin "1") (pinfunction "1_1") (pintype "passive"))
      (node (ref "Q1") (pin "2") (pinfunction "E_2") (pintype "passive"))
      (node (ref "R19") (pin "2") (pinfunction "2_2") (pintype "passive"))
      (node (ref "R2") (pin "1") (pinfunction "1_1") (pintype "passive"))
      (node (ref "RESET1") (pin "1") (pinfunction "1_1") (pintype "passive"))
      (node (ref "SWD1") (pin "2") (pinfunction "2_2") (pintype "passive"))
      (node (ref "U1") (pin "11") (pinfunction "FSYNC_11") (pintype "passive"))
      (node (ref "U1") (pin "18") (pinfunction "GND_18") (pintype "passive"))
      (node (ref "U1") (pin "20") (pinfunction "RESV_20") (pintype "passive"))
      (node (ref "U2") (pin "12") (pinfunction "VSSA_12") (pintype "passive"))
      (node (ref "U2") (pin "18") (pinfunction "VSS_18") (pintype "passive"))
      (node (ref "U2") (pin "63") (pinfunction "VSS_63") (pintype "passive"))
      (node (ref "U3") (pin "10") (pinfunction "PGND2_10") (pintype "passive"))
      (node (ref "U3") (pin "18") (pinfunction "GND_18") (pintype "passive"))
      (node (ref "U3") (pin "3") (pinfunction "PGND1_3") (pintype "passive"))
      (node (ref "U3") (pin "4") (pinfunction "PGND1_4") (pintype "passive"))
      (node (ref "U3") (pin "9") (pinfunction "PGND2_9") (pintype "passive"))
      (node (ref "USART1") (pin "2") (pinfunction "2_2") (pintype "passive"))
      (node (ref "V1") (pin "1") (pinfunction "GND_1") (pintype "passive"))
      (node (ref "V2") (pin "1") (pinfunction "GND_1") (pintype "passive"))
      (node (ref "X1") (pin "2") (pinfunction "2_2") (pintype "passive"))
      (node (ref "X1") (pin "4") (pinfunction "4_4") (pintype "passive"))
    )
    (net (code "47") (name "Net-(B1-GND)") (class "Default")
      (node (ref "B1") (pin "2") (pinfunction "GND_2") (pintype "passive"))
      (node (ref "Q1") (pin "3") (pinfunction "C_3") (pintype "passive"))
    )
    (net (code "48") (name "Net-(D1-A)") (class "Default")
      (node (ref "D1") (pin "2") (pinfunction "A_2") (pintype "passive"))
      (node (ref "R14") (pin "2") (pinfunction "2_2") (pintype "passive"))
    )
    (net (code "49") (name "Net-(D2-A)") (class "Default")
      (node (ref "D2") (pin "2") (pinfunction "A_2") (pintype "passive"))
      (node (ref "R15") (pin "2") (pinfunction "2_2") (pintype "passive"))
    )
    (net (code "50") (name "Net-(D3-A)") (class "Default")
      (node (ref "D3") (pin "2") (pinfunction "A_2") (pintype "passive"))
      (node (ref "R16") (pin "2") (pinfunction "2_2") (pintype "passive"))
    )
    (net (code "51") (name "Net-(D4-A)") (class "Default")
      (node (ref "D4") (pin "2") (pinfunction "A_2") (pintype "passive"))
      (node (ref "R17") (pin "2") (pinfunction "2_2") (pintype "passive"))
    )
    (net (code "52") (name "Net-(D5-A)") (class "Default")
      (node (ref "D5") (pin "2") (pinfunction "A_2") (pintype "passive"))
      (node (ref "R18") (pin "2") (pinfunction "2_2") (pintype "passive"))
    )
    (net (code "53") (name "Net-(POWER1-Pad2)") (class "Default")
      (node (ref "POWER1") (pin "2") (pinfunction "2_2") (pintype "passive"))
      (node (ref "S1") (pin "2") (pinfunction "2_2") (pintype "passive"))
    )
    (net (code "54") (name "Net-(Q1-B)") (class "Default")
      (node (ref "Q1") (pin "1") (pinfunction "B_1") (pintype "passive"))
      (node (ref "R4") (pin "1") (pinfunction "1_1") (pintype "passive"))
    )
    (net (code "55") (name "Net-(U2-BOOT0)") (class "Default")
      (node (ref "R2") (pin "2") (pinfunction "2_2") (pintype "passive"))
      (node (ref "U2") (pin "60") (pinfunction "BOOT0_60") (pintype "passive"))
    )
    (net (code "56") (name "Net-(U2-VCAP_1)") (class "Default")
      (node (ref "C10") (pin "1") (pinfunction "1_1") (pintype "passive"))
      (node (ref "U2") (pin "31") (pinfunction "VCAP_1_31") (pintype "passive"))
    )
    (net (code "57") (name "Net-(U2-VCAP_2)") (class "Default")
      (node (ref "C7") (pin "2") (pinfunction "2_2") (pintype "passive"))
      (node (ref "U2") (pin "47") (pinfunction "VCAP_2_47") (pintype "passive"))
    )
    (net (code "58") (name "VIN") (class "Default")
      (node (ref "C11") (pin "2") (pinfunction "2_2") (pintype "passive"))
      (node (ref "C19") (pin "2") (pinfunction "2_2") (pintype "passive"))
      (node (ref "C9") (pin "2") (pinfunction "2_2") (pintype "passive"))
      (node (ref "E1") (pin "1") (pinfunction "A_1") (pintype "passive"))
      (node (ref "E2") (pin "1") (pinfunction "A_1") (pintype "passive"))
      (node (ref "E4") (pin "1") (pinfunction "A_1") (pintype "passive"))
      (node (ref "R13") (pin "1") (pinfunction "1_1") (pintype "passive"))
      (node (ref "S1") (pin "3") (pinfunction "3_3") (pintype "passive"))
      (node (ref "U3") (pin "13") (pinfunction "VM2_13") (pintype "passive"))
      (node (ref "U3") (pin "14") (pinfunction "VM3_14") (pintype "passive"))
      (node (ref "U3") (pin "24") (pinfunction "VM1_24") (pintype "passive"))
      (node (ref "V1") (pin "3") (pinfunction "Vin_3") (pintype "passive"))
      (node (ref "V2") (pin "3") (pinfunction "Vin_3") (pintype "passive"))
    )
    (net (code "59") (name "unconnected-(M1-ADC-Pad2)") (class "Default")
      (node (ref "M1") (pin "2") (pinfunction "ADC_2") (pintype "passive+no_connect"))
    )
    (net (code "60") (name "unconnected-(M1-EN-Pad3)") (class "Default")
      (node (ref "M1") (pin "3") (pinfunction "EN_3") (pintype "passive+no_connect"))
    )
    (net (code "61") (name "unconnected-(M1-GPIO0-Pad12)") (class "Default")
      (node (ref "M1") (pin "12") (pinfunction "GPIO0_12") (pintype "passive+no_connect"))
    )
    (net (code "62") (name "unconnected-(M1-GPIO2-Pad11)") (class "Default")
      (node (ref "M1") (pin "11") (pinfunction "GPIO2_11") (pintype "passive+no_connect"))
    )
    (net (code "63") (name "unconnected-(M1-GPIO4-Pad13)") (class "Default")
      (node (ref "M1") (pin "13") (pinfunction "GPIO4_13") (pintype "passive+no_connect"))
    )
    (net (code "64") (name "unconnected-(M1-GPIO5-Pad14)") (class "Default")
      (node (ref "M1") (pin "14") (pinfunction "GPIO5_14") (pintype "passive+no_connect"))
    )
    (net (code "65") (name "unconnected-(M1-GPIO12-Pad6)") (class "Default")
      (node (ref "M1") (pin "6") (pinfunction "GPIO12_6") (pintype "passive+no_connect"))
    )
    (net (code "66") (name "unconnected-(M1-GPIO13-Pad7)") (class "Default")
      (node (ref "M1") (pin "7") (pinfunction "GPIO13_7") (pintype "passive+no_connect"))
    )
    (net (code "67") (name "unconnected-(M1-GPIO14-Pad5)") (class "Default")
      (node (ref "M1") (pin "5") (pinfunction "GPIO14_5") (pintype "passive+no_connect"))
    )
    (net (code "68") (name "unconnected-(M1-GPIO15-Pad10)") (class "Default")
      (node (ref "M1") (pin "10") (pinfunction "GPIO15_10") (pintype "passive+no_connect"))
    )
    (net (code "69") (name "unconnected-(M1-GPIO16-Pad4)") (class "Default")
      (node (ref "M1") (pin "4") (pinfunction "GPIO16_4") (pintype "passive+no_connect"))
    )
    (net (code "70") (name "unconnected-(M1-RST-Pad1)") (class "Default")
      (node (ref "M1") (pin "1") (pinfunction "RST_1") (pintype "passive+no_connect"))
    )
    (net (code "71") (name "unconnected-(S1-Pad1)") (class "Default")
      (node (ref "S1") (pin "1") (pinfunction "1_1") (pintype "passive"))
    )
    (net (code "72") (name "unconnected-(U1-AUX_CL-Pad7)") (class "Default")
      (node (ref "U1") (pin "7") (pinfunction "AUX_CL_7") (pintype "passive+no_connect"))
    )
    (net (code "73") (name "unconnected-(U1-AUX_DA-Pad21)") (class "Default")
      (node (ref "U1") (pin "21") (pinfunction "AUX_DA_21") (pintype "passive+no_connect"))
    )
    (net (code "74") (name "unconnected-(U1-NC-Pad2)") (class "Default")
      (node (ref "U1") (pin "2") (pinfunction "NC_2") (pintype "passive+no_connect"))
    )
    (net (code "75") (name "unconnected-(U1-NC-Pad3)") (class "Default")
      (node (ref "U1") (pin "3") (pinfunction "NC_3") (pintype "passive+no_connect"))
    )
    (net (code "76") (name "unconnected-(U1-NC-Pad4)") (class "Default")
      (node (ref "U1") (pin "4") (pinfunction "NC_4") (pintype "passive+no_connect"))
    )
    (net (code "77") (name "unconnected-(U1-NC-Pad5)") (class "Default")
      (node (ref "U1") (pin "5") (pinfunction "NC_5") (pintype "passive+no_connect"))
    )
    (net (code "78") (name "unconnected-(U1-NC-Pad6)") (class "Default")
      (node (ref "U1") (pin "6") (pinfunction "NC_6") (pintype "passive+no_connect"))
    )
    (net (code "79") (name "unconnected-(U1-NC-Pad14)") (class "Default")
      (node (ref "U1") (pin "14") (pinfunction "NC_14") (pintype "passive+no_connect"))
    )
    (net (code "80") (name "unconnected-(U1-NC-Pad15)") (class "Default")
      (node (ref "U1") (pin "15") (pinfunction "NC_15") (pintype "passive+no_connect"))
    )
    (net (code "81") (name "unconnected-(U1-NC-Pad16)") (class "Default")
      (node (ref "U1") (pin "16") (pinfunction "NC_16") (pintype "passive+no_connect"))
    )
    (net (code "82") (name "unconnected-(U1-NC-Pad17)") (class "Default")
      (node (ref "U1") (pin "17") (pinfunction "NC_17") (pintype "passive+no_connect"))
    )
    (net (code "83") (name "unconnected-(U1-RESV-Pad19)") (class "Default")
      (node (ref "U1") (pin "19") (pinfunction "RESV_19") (pintype "passive+no_connect"))
    )
    (net (code "84") (name "unconnected-(U2-PA10-Pad43)") (class "Default")
      (node (ref "U2") (pin "43") (pinfunction "PA10_43") (pintype "passive"))
    )
    (net (code "85") (name "unconnected-(U2-PA11-Pad44)") (class "Default")
      (node (ref "U2") (pin "44") (pinfunction "PA11_44") (pintype "passive"))
    )
    (net (code "86") (name "unconnected-(U2-PA12-Pad45)") (class "Default")
      (node (ref "U2") (pin "45") (pinfunction "PA12_45") (pintype "passive"))
    )
    (net (code "87") (name "unconnected-(U2-PA15-Pad50)") (class "Default")
      (node (ref "U2") (pin "50") (pinfunction "PA15_50") (pintype "passive"))
    )
    (net (code "88") (name "unconnected-(U2-PB5-Pad57)") (class "Default")
      (node (ref "U2") (pin "57") (pinfunction "PB5_57") (pintype "passive"))
    )
    (net (code "89") (name "unconnected-(U2-PB15-Pad36)") (class "Default")
      (node (ref "U2") (pin "36") (pinfunction "PB15_36") (pintype "passive"))
    )
    (net (code "90") (name "unconnected-(U2-PC0-Pad8)") (class "Default")
      (node (ref "U2") (pin "8") (pinfunction "PC0_8") (pintype "passive"))
    )
    (net (code "91") (name "unconnected-(U2-PC4-Pad24)") (class "Default")
      (node (ref "U2") (pin "24") (pinfunction "PC4_24") (pintype "passive"))
    )
    (net (code "92") (name "unconnected-(U2-PC8-Pad39)") (class "Default")
      (node (ref "U2") (pin "39") (pinfunction "PC8_39") (pintype "passive"))
    )
    (net (code "93") (name "unconnected-(U2-PC9-Pad40)") (class "Default")
      (node (ref "U2") (pin "40") (pinfunction "PC9_40") (pintype "passive"))
    )
    (net (code "94") (name "unconnected-(U2-PC12-Pad53)") (class "Default")
      (node (ref "U2") (pin "53") (pinfunction "PC12_53") (pintype "passive"))
    )
    (net (code "95") (name "unconnected-(U2-PC13-Pad2)") (class "Default")
      (node (ref "U2") (pin "2") (pinfunction "PC13_2") (pintype "passive"))
    )
    (net (code "96") (name "unconnected-(U2-PC14-Pad3)") (class "Default")
      (node (ref "U2") (pin "3") (pinfunction "PC14_3") (pintype "passive"))
    )
    (net (code "97") (name "unconnected-(U2-PC15-Pad4)") (class "Default")
      (node (ref "U2") (pin "4") (pinfunction "PC15_4") (pintype "passive"))
    )
    (net (code "98") (name "unconnected-(U2-PD2-Pad54)") (class "Default")
      (node (ref "U2") (pin "54") (pinfunction "PD2_54") (pintype "passive"))
    )
  )
)
